# VentillatorCircuit.net
KiCad netlist of a schematic drawn in EAGLE
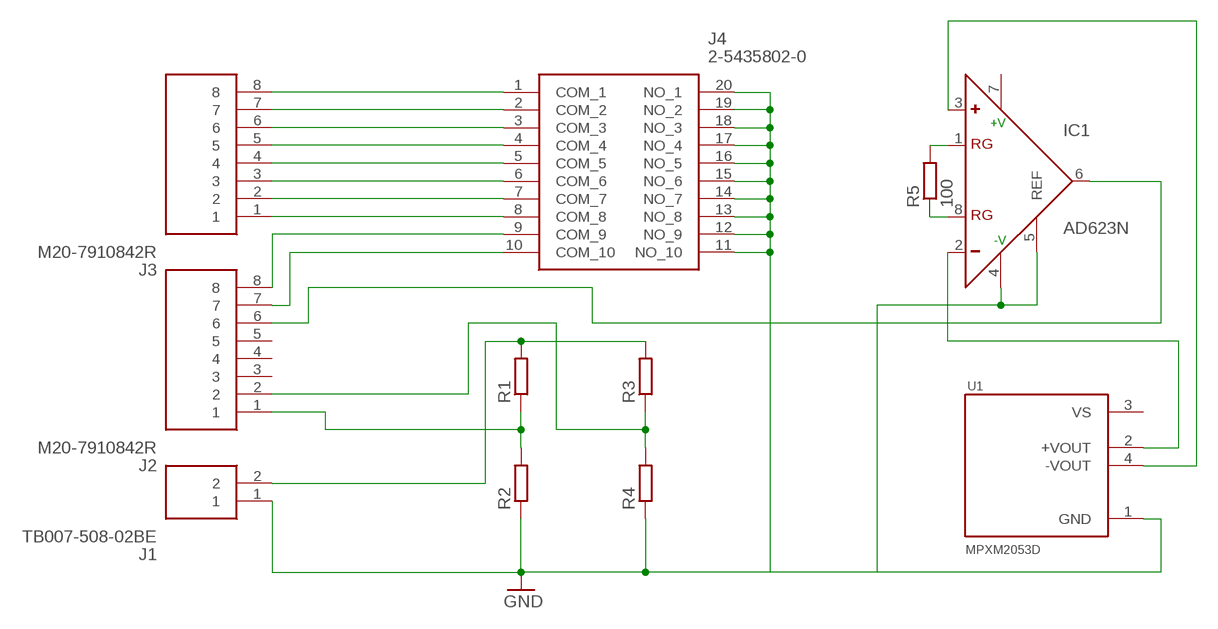
[diagram p0: schematic, sheet 1]

(export (version "E")
  (design (tool "Eeschema 10.0.6"))
  (components
    (comp (ref "IC1")
      (value "AD623N")
      (footprint "eagle-import:DIL08")
      (fields (field (name "MF") "ALTERA CORPORATION") (field (name "MPN") "AD623ANZ"))
      (libsource (lib "eagle-import") (part "AD623N"))
    )
    (comp (ref "J1")
      (value "TB007-508-02BE")
      (footprint "eagle-import:TB00750802BE")
      (fields (field (name "MOUSER_PART_NUMBER") "490-TB007-508-02BE"))
      (libsource (lib "eagle-import") (part "TB007-508-02BE"))
    )
    (comp (ref "J2")
      (value "M20-7910842R")
      (footprint "eagle-import:M207910842R")
      (fields (field (name "MOUSER_PART_NUMBER") "855-M20-7910842R"))
      (libsource (lib "eagle-import") (part "M20-7910842R"))
    )
    (comp (ref "J3")
      (value "M20-7910842R")
      (footprint "eagle-import:M207910842R")
      (fields (field (name "MOUSER_PART_NUMBER") "855-M20-7910842R"))
      (libsource (lib "eagle-import") (part "M20-7910842R"))
    )
    (comp (ref "J4")
      (value "2-5435802-0")
      (footprint "eagle-import:254358020")
      (fields (field (name "MOUSER_PART_NUMBER") "506-2-5435802-0"))
      (libsource (lib "eagle-import") (part "2-5435802-0"))
    )
    (comp (ref "R1")
      (value "R-EU_0207/12")
      (footprint "eagle-import:0207_12")
      (libsource (lib "eagle-import") (part "R-EU_0207/12"))
    )
    (comp (ref "R2")
      (value "R-EU_0207/12")
      (footprint "eagle-import:0207_12")
      (libsource (lib "eagle-import") (part "R-EU_0207/12"))
    )
    (comp (ref "R3")
      (value "R-EU_0207/12")
      (footprint "eagle-import:0207_12")
      (libsource (lib "eagle-import") (part "R-EU_0207/12"))
    )
    (comp (ref "R4")
      (value "R-EU_0207/12")
      (footprint "eagle-import:0207_12")
      (libsource (lib "eagle-import") (part "R-EU_0207/12"))
    )
    (comp (ref "R5")
      (value "100")
      (footprint "eagle-import:0207_12")
      (libsource (lib "eagle-import") (part "R-EU_0207/12"))
    )
    (comp (ref "U1")
      (value "MPXM2053D")
      (footprint "eagle-import:SOT127P1219X419-5N")
      (fields (field (name "MF") "Freescale Semiconductor"))
      (libsource (lib "eagle-import") (part "MPXM2053D"))
    )
  )
  (nets
    (net (code "1") (name "/+V") (class "Default")
      (node (ref "IC1") (pin "7") (pinfunction "+V_7") (pintype "power_in"))
    )
    (net (code "2") (name "/VS") (class "Default")
      (node (ref "U1") (pin "3") (pinfunction "VS_3") (pintype "power_in"))
    )
    (net (code "3") (name "GND") (class "Default")
      (node (ref "IC1") (pin "4") (pinfunction "-V_4") (pintype "power_in"))
      (node (ref "IC1") (pin "5") (pinfunction "REF_5") (pintype "passive"))
      (node (ref "J1") (pin "1") (pinfunction "1_1") (pintype "bidirectional"))
      (node (ref "J4") (pin "11") (pinfunction "NO_10_11") (pintype "bidirectional"))
      (node (ref "J4") (pin "12") (pinfunction "NO_9_12") (pintype "bidirectional"))
      (node (ref "J4") (pin "13") (pinfunction "NO_8_13") (pintype "bidirectional"))
      (node (ref "J4") (pin "14") (pinfunction "NO_7_14") (pintype "bidirectional"))
      (node (ref "J4") (pin "15") (pinfunction "NO_6_15") (pintype "bidirectional"))
      (node (ref "J4") (pin "16") (pinfunction "NO_5_16") (pintype "bidirectional"))
      (node (ref "J4") (pin "17") (pinfunction "NO_4_17") (pintype "bidirectional"))
      (node (ref "J4") (pin "18") (pinfunction "NO_3_18") (pintype "bidirectional"))
      (node (ref "J4") (pin "19") (pinfunction "NO_2_19") (pintype "bidirectional"))
      (node (ref "J4") (pin "20") (pinfunction "NO_1_20") (pintype "bidirectional"))
      (node (ref "R2") (pin "1") (pinfunction "1_1") (pintype "passive"))
      (node (ref "R4") (pin "1") (pinfunction "1_1") (pintype "passive"))
      (node (ref "U1") (pin "1") (pinfunction "GND_1") (pintype "power_in"))
    )
    (net (code "4") (name "Net-(IC1-+)") (class "Default")
      (node (ref "IC1") (pin "3") (pinfunction "+_3") (pintype "input"))
      (node (ref "U1") (pin "4") (pinfunction "-VOUT_4") (pintype "output"))
    )
    (net (code "5") (name "Net-(IC1--)") (class "Default")
      (node (ref "IC1") (pin "2") (pinfunction "-_2") (pintype "input"))
      (node (ref "U1") (pin "2") (pinfunction "+VOUT_2") (pintype "output"))
    )
    (net (code "6") (name "Net-(IC1-OUT)") (class "Default")
      (node (ref "IC1") (pin "6") (pinfunction "OUT_6") (pintype "output"))
      (node (ref "J2") (pin "6") (pinfunction "6_6") (pintype "bidirectional"))
    )
    (net (code "7") (name "Net-(IC1-RG-Pad1)") (class "Default")
      (node (ref "IC1") (pin "1") (pinfunction "RG_1") (pintype "passive"))
      (node (ref "R5") (pin "2") (pinfunction "2_2") (pintype "passive"))
    )
    (net (code "8") (name "Net-(IC1-RG-Pad8)") (class "Default")
      (node (ref "IC1") (pin "8") (pinfunction "RG_8") (pintype "passive"))
      (node (ref "R5") (pin "1") (pinfunction "1_1") (pintype "passive"))
    )
    (net (code "9") (name "Net-(J1-Pad2)") (class "Default")
      (node (ref "J1") (pin "2") (pinfunction "2_2") (pintype "bidirectional"))
      (node (ref "R1") (pin "2") (pinfunction "2_2") (pintype "passive"))
      (node (ref "R3") (pin "2") (pinfunction "2_2") (pintype "passive"))
    )
    (net (code "10") (name "Net-(J2-Pad1)") (class "Default")
      (node (ref "J2") (pin "1") (pinfunction "1_1") (pintype "bidirectional"))
      (node (ref "R1") (pin "1") (pinfunction "1_1") (pintype "passive"))
      (node (ref "R2") (pin "2") (pinfunction "2_2") (pintype "passive"))
    )
    (net (code "11") (name "Net-(J2-Pad2)") (class "Default")
      (node (ref "J2") (pin "2") (pinfunction "2_2") (pintype "bidirectional"))
      (node (ref "R3") (pin "1") (pinfunction "1_1") (pintype "passive"))
      (node (ref "R4") (pin "2") (pinfunction "2_2") (pintype "passive"))
    )
    (net (code "12") (name "Net-(J4-COM_1)") (class "Default")
      (node (ref "J3") (pin "8") (pinfunction "8_8") (pintype "bidirectional"))
      (node (ref "J4") (pin "1") (pinfunction "COM_1_1") (pintype "bidirectional"))
    )
    (net (code "13") (name "Net-(J4-COM_2)") (class "Default")
      (node (ref "J3") (pin "7") (pinfunction "7_7") (pintype "bidirectional"))
      (node (ref "J4") (pin "2") (pinfunction "COM_2_2") (pintype "bidirectional"))
    )
    (net (code "14") (name "Net-(J4-COM_3)") (class "Default")
      (node (ref "J3") (pin "6") (pinfunction "6_6") (pintype "bidirectional"))
      (node (ref "J4") (pin "3") (pinfunction "COM_3_3") (pintype "bidirectional"))
    )
    (net (code "15") (name "Net-(J4-COM_4)") (class "Default")
      (node (ref "J3") (pin "5") (pinfunction "5_5") (pintype "bidirectional"))
      (node (ref "J4") (pin "4") (pinfunction "COM_4_4") (pintype "bidirectional"))
    )
    (net (code "16") (name "Net-(J4-COM_5)") (class "Default")
      (node (ref "J3") (pin "4") (pinfunction "4_4") (pintype "bidirectional"))
      (node (ref "J4") (pin "5") (pinfunction "COM_5_5") (pintype "bidirectional"))
    )
    (net (code "17") (name "Net-(J4-COM_6)") (class "Default")
      (node (ref "J3") (pin "3") (pinfunction "3_3") (pintype "bidirectional"))
      (node (ref "J4") (pin "6") (pinfunction "COM_6_6") (pintype "bidirectional"))
    )
    (net (code "18") (name "Net-(J4-COM_7)") (class "Default")
      (node (ref "J3") (pin "2") (pinfunction "2_2") (pintype "bidirectional"))
      (node (ref "J4") (pin "7") (pinfunction "COM_7_7") (pintype "bidirectional"))
    )
    (net (code "19") (name "Net-(J4-COM_8)") (class "Default")
      (node (ref "J3") (pin "1") (pinfunction "1_1") (pintype "bidirectional"))
      (node (ref "J4") (pin "8") (pinfunction "COM_8_8") (pintype "bidirectional"))
    )
    (net (code "20") (name "Net-(J4-COM_9)") (class "Default")
      (node (ref "J2") (pin "8") (pinfunction "8_8") (pintype "bidirectional"))
      (node (ref "J4") (pin "9") (pinfunction "COM_9_9") (pintype "bidirectional"))
    )
    (net (code "21") (name "Net-(J4-COM_10)") (class "Default")
      (node (ref "J2") (pin "7") (pinfunction "7_7") (pintype "bidirectional"))
      (node (ref "J4") (pin "10") (pinfunction "COM_10_10") (pintype "bidirectional"))
    )
    (net (code "22") (name "unconnected-(J2-Pad3)") (class "Default")
      (node (ref "J2") (pin "3") (pinfunction "3_3") (pintype "bidirectional"))
    )
    (net (code "23") (name "unconnected-(J2-Pad4)") (class "Default")
      (node (ref "J2") (pin "4") (pinfunction "4_4") (pintype "bidirectional"))
    )
    (net (code "24") (name "unconnected-(J2-Pad5)") (class "Default")
      (node (ref "J2") (pin "5") (pinfunction "5_5") (pintype "bidirectional"))
    )
  )
)
